# stm32_board.net
KiCad netlist of a schematic drawn in Altium Designer
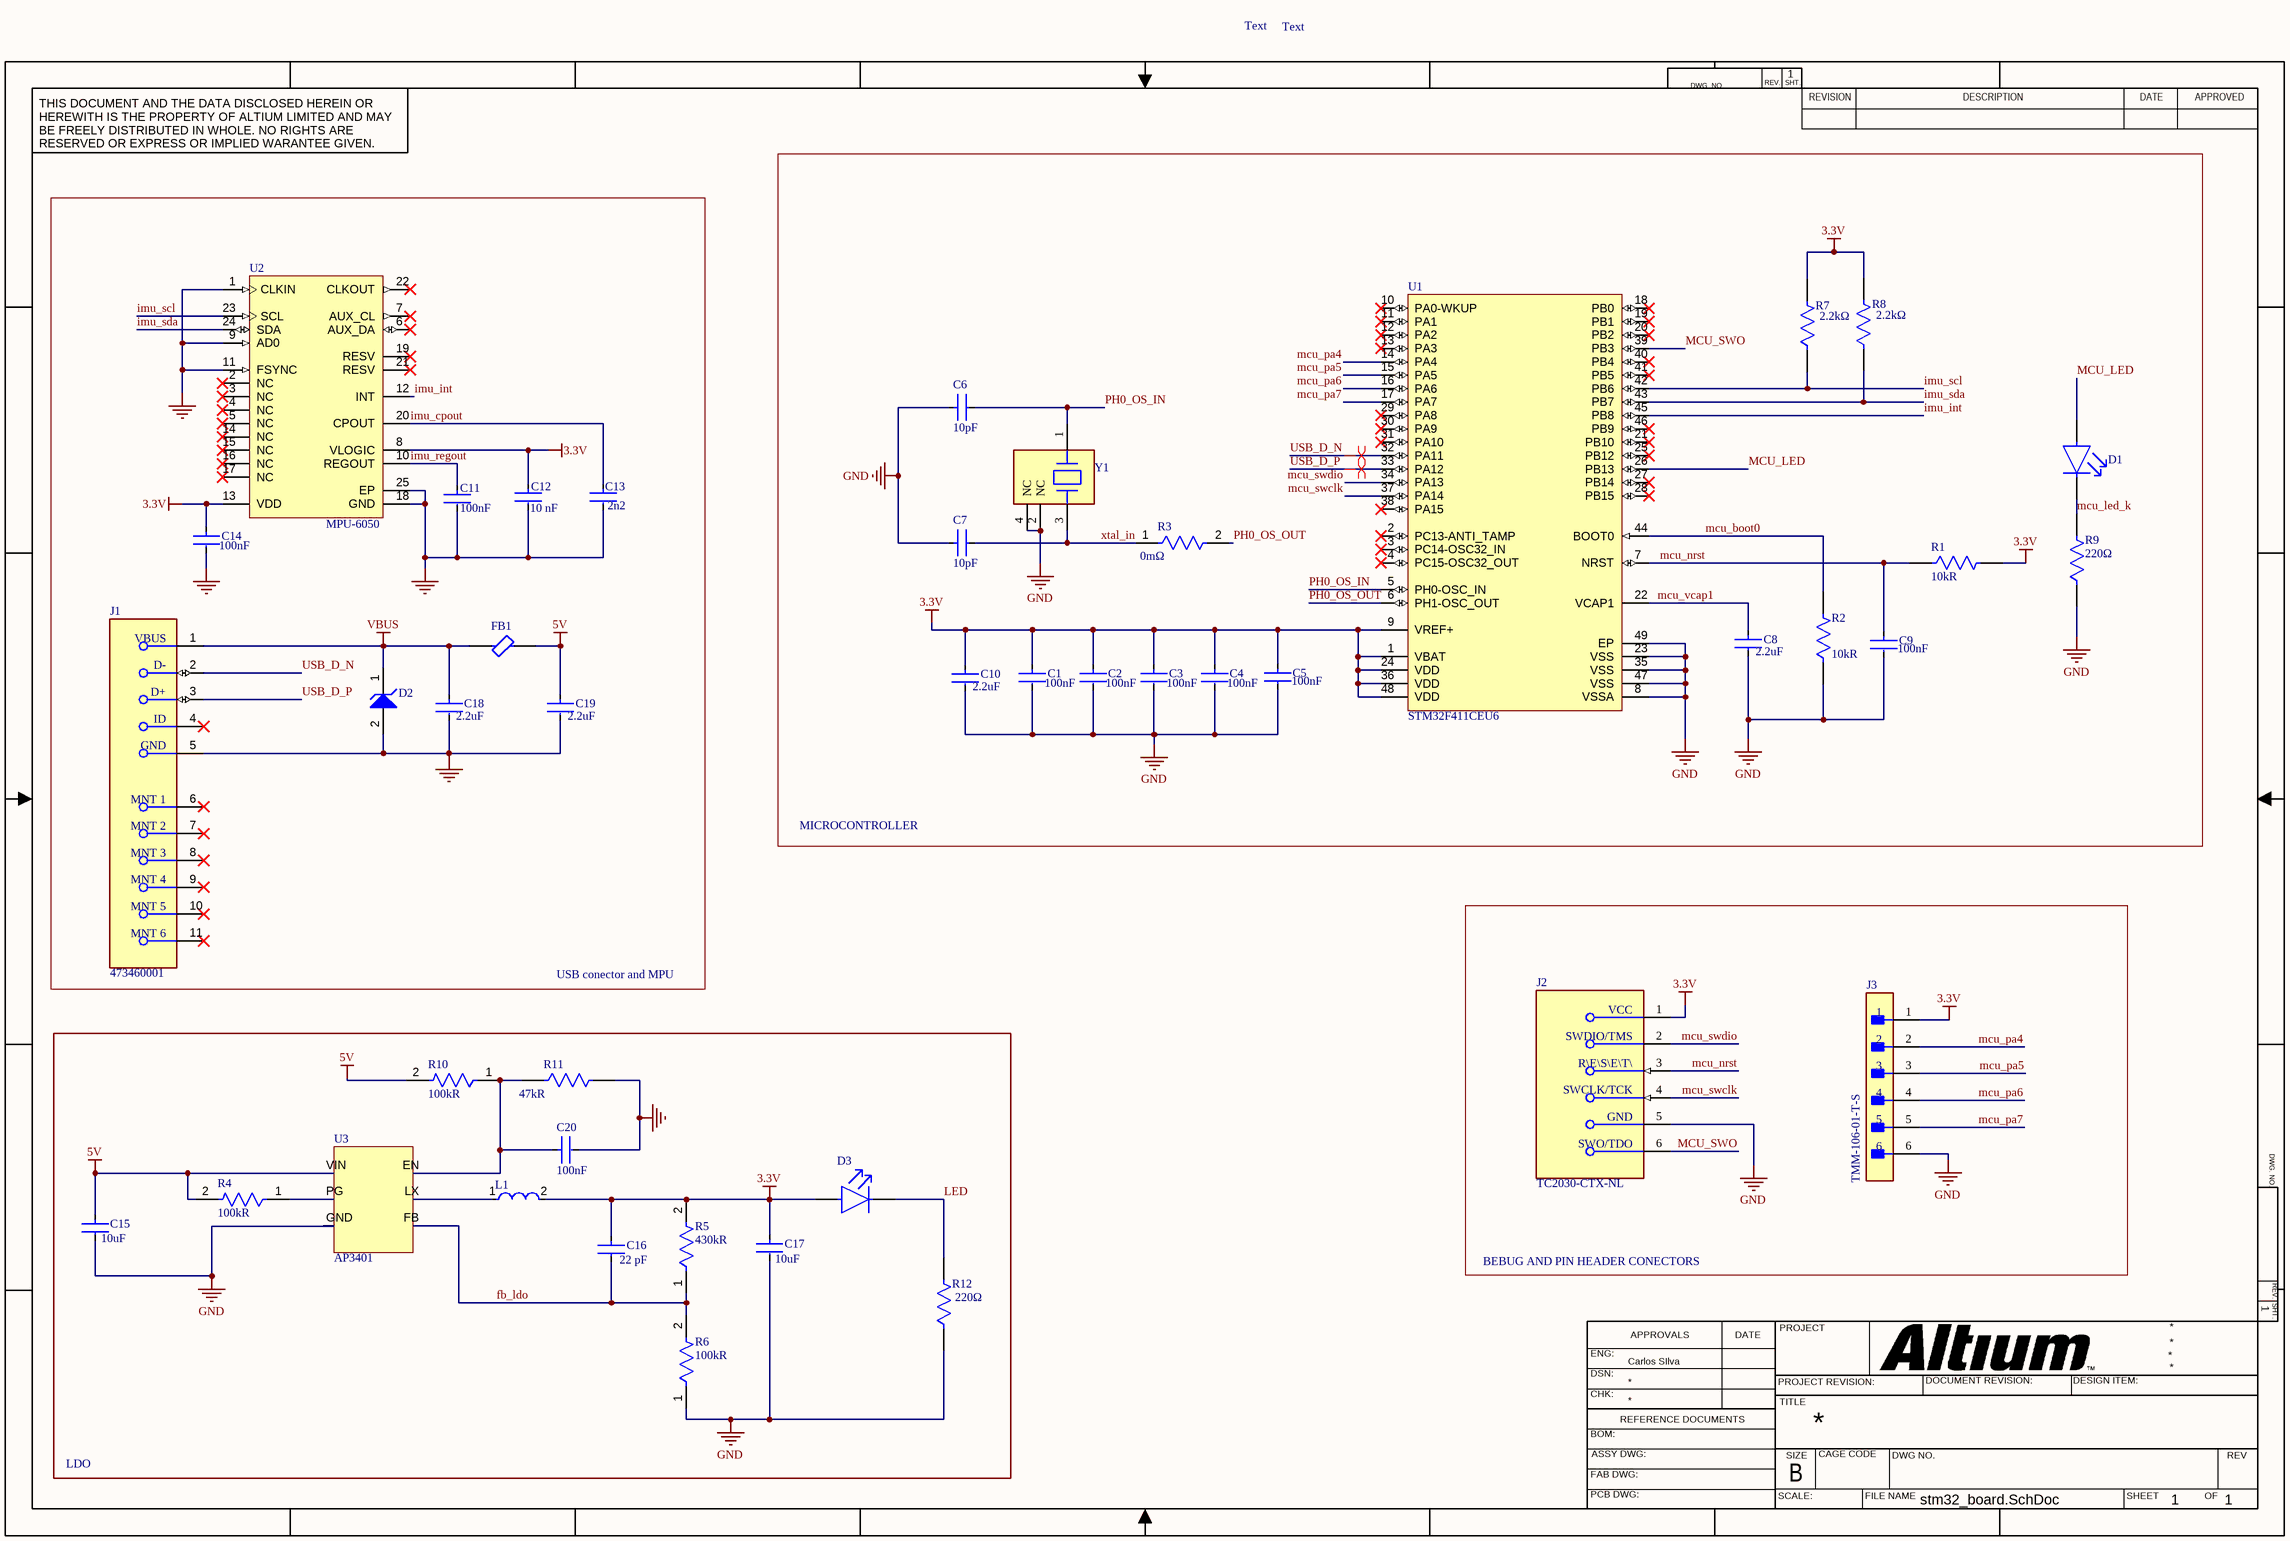
[diagram p0: stm32_board.SchDoc]

(export (version "E")
  (design (tool "Eeschema 10.0.6"))
  (components
    (comp (ref "C1")
      (value "CL05B104KP5NNNC")
      (footprint "FP-CL17-IPC_C")
      (description "Cap Ceramic 100nF 10V X7R ±10% SMD 0402 +125°C Paper T/R")
      (fields (field (name "CAPACITANCE") "100nF") (field (name "TOLERANCE") "10%"))
      (libsource (lib "Altium Content Vault") (part "b4654b650e69147ec39a6b967a45e02"))
    )
    (comp (ref "C2")
      (value "CL05B104KP5NNNC")
      (footprint "FP-CL17-IPC_C")
      (description "Cap Ceramic 100nF 10V X7R ±10% SMD 0402 +125°C Paper T/R")
      (fields (field (name "CAPACITANCE") "100nF") (field (name "TOLERANCE") "10%"))
      (libsource (lib "Altium Content Vault") (part "b4654b650e69147ec39a6b967a45e02"))
    )
    (comp (ref "C3")
      (value "CL05B104KP5NNNC")
      (footprint "FP-CL17-IPC_C")
      (description "Cap Ceramic 100nF 10V X7R ±10% SMD 0402 +125°C Paper T/R")
      (fields (field (name "CAPACITANCE") "100nF") (field (name "TOLERANCE") "10%"))
      (libsource (lib "Altium Content Vault") (part "b4654b650e69147ec39a6b967a45e02"))
    )
    (comp (ref "C4")
      (value "CL05B104KP5NNNC")
      (footprint "FP-CL17-IPC_C")
      (description "Cap Ceramic 100nF 10V X7R ±10% SMD 0402 +125°C Paper T/R")
      (fields (field (name "CAPACITANCE") "100nF") (field (name "TOLERANCE") "10%"))
      (libsource (lib "Altium Content Vault") (part "b4654b650e69147ec39a6b967a45e02"))
    )
    (comp (ref "C5")
      (value "CL05B104KP5NNNC")
      (footprint "FP-CL17-IPC_C")
      (description "Cap Ceramic 100nF 10V X7R ±10% SMD 0402 +125°C Paper T/R")
      (fields (field (name "CAPACITANCE") "100nF") (field (name "TOLERANCE") "10%"))
      (libsource (lib "Altium Content Vault") (part "b4654b650e69147ec39a6b967a45e02"))
    )
    (comp (ref "C6")
      (value "GRM0225C1C100JA03L")
      (footprint "FP-GRM022-0_02-IPC_C")
      (description "Chip Multilayer Ceramic Capacitors for General Purpose, 01005, 10pF, C0G, 30ppm/°C, 5%, 16V")
      (fields (field (name "CAPACITANCE") "10pF") (field (name "TOLERANCE") "5%"))
      (libsource (lib "Altium Content Vault") (part "02cd4be3c70576c341d710602a673aa"))
    )
    (comp (ref "C7")
      (value "GRM0225C1C100JA03L")
      (footprint "FP-GRM022-0_02-IPC_C")
      (description "Chip Multilayer Ceramic Capacitors for General Purpose, 01005, 10pF, C0G, 30ppm/°C, 5%, 16V")
      (fields (field (name "CAPACITANCE") "10pF") (field (name "TOLERANCE") "5%"))
      (libsource (lib "Altium Content Vault") (part "02cd4be3c70576c341d710602a673aa"))
    )
    (comp (ref "C8")
      (value "GRM155D71A225ME15D")
      (footprint "FP-GRM155-0_2-0_05-IPC_A")
      (description "Chip Multilayer Ceramic Capacitors for General Purpose, 0402, 2.2uF, X7T, +22%/-33%, 20%, 10V")
      (fields (field (name "TOLERANCE") "20%") (field (name "CAPACITANCE") "2.2uF"))
      (libsource (lib "Altium Content Vault") (part "b4654b650e69147ec39a6b967a45e02"))
    )
    (comp (ref "C9")
      (value "CL05B104KP5NNNC")
      (footprint "FP-CL17-IPC_C")
      (description "Cap Ceramic 100nF 10V X7R ±10% SMD 0402 +125°C Paper T/R")
      (fields (field (name "CAPACITANCE") "100nF") (field (name "TOLERANCE") "10%"))
      (libsource (lib "Altium Content Vault") (part "b4654b650e69147ec39a6b967a45e02"))
    )
    (comp (ref "C10")
      (value "GRM155D71A225ME15D")
      (footprint "FP-GRM155-0_2-0_05-IPC_A")
      (description "Chip Multilayer Ceramic Capacitors for General Purpose, 0402, 2.2uF, X7T, +22%/-33%, 20%, 10V")
      (fields (field (name "TOLERANCE") "20%") (field (name "CAPACITANCE") "2.2uF"))
      (libsource (lib "Altium Content Vault") (part "b4654b650e69147ec39a6b967a45e02"))
    )
    (comp (ref "C11")
      (value "CL05B104KP5NNNC")
      (footprint "FP-CL17-IPC_C")
      (description "Cap Ceramic 100nF 10V X7R ±10% SMD 0402 +125°C Paper T/R")
      (fields (field (name "CAPACITANCE") "100nF") (field (name "TOLERANCE") "10%"))
      (libsource (lib "Altium Content Vault") (part "b4654b650e69147ec39a6b967a45e02"))
    )
    (comp (ref "C12")
      (value "C0603C103K5RACTU")
      (footprint "FP-C0603C-CF-MFG")
      (description "CAP CER 10000PF 50V X7R 0603")
      (fields
        (field (name "MANUFACTURER") "KEMET")
        (field (name "CAPACITANCE") "10 nF")
        (field (name "OCTOPART") "https://octopart.com/c0603c103k5ractu-kemet-133094")
      )
      (libsource (lib "Altium Content Vault") (part "b4654b650e69147ec39a6b967a45e02"))
    )
    (comp (ref "C13")
      (value "2n2")
      (footprint "FP-C0402-BB-MFG")
      (description "CAP CER 2200PF 16V NP0 0402")
      (fields
        (field (name "OCTOPART") "https://octopart.com/c0402c222f4gactu-kemet-12823119")
        (field (name "MANUFACTURER") "Kemet")
      )
      (libsource (lib "Altium Content Vault") (part "b4654b650e69147ec39a6b967a45e02"))
    )
    (comp (ref "C14")
      (value "CL05B104KP5NNNC")
      (footprint "FP-CL17-IPC_C")
      (description "Cap Ceramic 100nF 10V X7R ±10% SMD 0402 +125°C Paper T/R")
      (fields (field (name "CAPACITANCE") "100nF") (field (name "TOLERANCE") "10%"))
      (libsource (lib "Altium Content Vault") (part "b4654b650e69147ec39a6b967a45e02"))
    )
    (comp (ref "C15")
      (value "LMK107BBJ106MALT")
      (footprint "FP-0603-L_1_6_0_2-W_0_8_0-IPC_A")
      (description "Multilayer Ceramic Capacitor 10uF 10V X5R 20% SMD 0603 T/R")
      (fields
        (field (name "VOLTAGE") "10V")
        (field (name "TOLERANCE") "20%")
        (field (name "CAPACITANCE") "10uF")
      )
      (libsource (lib "Altium Content Vault") (part "b4654b650e69147ec39a6b967a45e02"))
    )
    (comp (ref "C16")
      (value "C0603C220J5GACTU")
      (footprint "FP-C0603C-CF-MFG")
      (description "Cap Ceramic 22pF 50V C0G 5% SMD 0603 125°C Paper T/R")
      (fields
        (field (name "CAPACITANCE") "22 pF")
        (field (name "TOLERANCE") "0.05")
        (field (name "MANUFACTURER") "KEMET")
      )
      (libsource (lib "Altium Content Vault") (part "b4654b650e69147ec39a6b967a45e02"))
    )
    (comp (ref "C17")
      (value "LMK107BBJ106MALT")
      (footprint "FP-0603-L_1_6_0_2-W_0_8_0-IPC_A")
      (description "Multilayer Ceramic Capacitor 10uF 10V X5R 20% SMD 0603 T/R")
      (fields
        (field (name "VOLTAGE") "10V")
        (field (name "TOLERANCE") "20%")
        (field (name "CAPACITANCE") "10uF")
      )
      (libsource (lib "Altium Content Vault") (part "b4654b650e69147ec39a6b967a45e02"))
    )
    (comp (ref "C18")
      (value "GRM155D71A225ME15D")
      (footprint "FP-GRM155-0_2-0_05-IPC_A")
      (description "Chip Multilayer Ceramic Capacitors for General Purpose, 0402, 2.2uF, X7T, +22%/-33%, 20%, 10V")
      (fields (field (name "TOLERANCE") "20%") (field (name "CAPACITANCE") "2.2uF"))
      (libsource (lib "Altium Content Vault") (part "b4654b650e69147ec39a6b967a45e02"))
    )
    (comp (ref "C19")
      (value "GRM155D71A225ME15D")
      (footprint "FP-GRM155-0_2-0_05-IPC_A")
      (description "Chip Multilayer Ceramic Capacitors for General Purpose, 0402, 2.2uF, X7T, +22%/-33%, 20%, 10V")
      (fields (field (name "TOLERANCE") "20%") (field (name "CAPACITANCE") "2.2uF"))
      (libsource (lib "Altium Content Vault") (part "b4654b650e69147ec39a6b967a45e02"))
    )
    (comp (ref "C20")
      (value "CL05B104KP5NNNC")
      (footprint "FP-CL17-IPC_C")
      (description "Cap Ceramic 100nF 10V X7R ±10% SMD 0402 +125°C Paper T/R")
      (fields (field (name "CAPACITANCE") "100nF") (field (name "TOLERANCE") "10%"))
      (libsource (lib "Altium Content Vault") (part "b4654b650e69147ec39a6b967a45e02"))
    )
    (comp (ref "D1")
      (value "LTST-C190GKT")
      (footprint "FP-LTST-C190GKT-MFG")
      (description "LED GREEN CLEAR CHIP SMD")
      (fields (field (name "VOLTAGE") "2V"))
      (libsource (lib "Altium Content Vault") (part "8706943c75ba83719d021d2fdc84c58"))
    )
    (comp (ref "D2")
      (value "ESD9X5.0ST5G")
      (footprint "ONSC-SOD-923-2-514AA-01_V")
      (fields (field (name "MANUFACTURER") "On Semiconductor"))
      (libsource (lib "Altium Content Vault") (part "ONSC-K1A2-2"))
    )
    (comp (ref "D3")
      (value "LTST-C190GKT")
      (footprint "FP-LTST-C190GKT-MFG")
      (description "LED GREEN CLEAR CHIP SMD")
      (fields (field (name "VOLTAGE") "2V"))
      (libsource (lib "Altium Content Vault") (part "8706943c75ba83719d021d2fdc84c58"))
    )
    (comp (ref "FB1")
      (value "BLM18KG121TN1D")
      (footprint "FP-BLM18-0_15-t0_6-d1_2-IPC_A")
      (description "FERRITE BEAD 120 OHM 0603 1LN")
      (fields (field (name "TOLERANCE") "25%"))
      (libsource (lib "Altium Content Vault") (part "5f30dd21d616792df468990f7003faa"))
    )
    (comp (ref "J1")
      (value "473460001")
      (footprint "FP-473460001-MFG")
      (description "CONN RCPT USB2.0 MICRO B SMD R/A")
      (fields
        (field (name "OCTOPART") "https://octopart.com/47346-0001-molex-7164928")
        (field (name "MANUFACTURER") "Molex")
      )
      (libsource (lib "Altium Content Vault") (part "53ae1f1d9b557310b43ca686e5bb76a"))
    )
    (comp (ref "J2")
      (value "TC2030-CTX-NL")
      (footprint "FP-TC2030-CTX-NL-MFG")
      (description "6-Pin “No legs” TC2030 Plug-of-Nails™ Cable for use with ARM Cortex processors")
      (libsource (lib "Altium Content Vault") (part "e3fe093a55dc37473f431e03719485e"))
    )
    (comp (ref "J3")
      (value "TMM-106-01-T-S")
      (footprint "FP-TMM-106-01-T-S-MFG")
      (description "CONN HEADER VERT 6POS 2MM")
      (libsource (lib "Altium Content Vault") (part "f2cb566baf1c37ab5a3b8e90bbeafd6"))
    )
    (comp (ref "L1")
      (value "LQM2MPN2R2NG0L")
      (footprint "FP-LQM2MPN_G0-MFG")
      (description "Multilayer Type Inductor for Power Lines, 0806 (2016), 2.2μH, 30%, 0.138Ω, 1.2A")
      (fields (field (name "TOLERANCE") "30%"))
      (libsource (lib "Altium Content Vault") (part "725321dda6339637d4d059423bc1c3c"))
    )
    (comp (ref "R1")
      (value "RMCF0603FT10K0")
      (footprint "FP-RMCF0603-MFG")
      (description "10kΩ ±1% 0.1W 0603 Thick Film Chip Resistor AEC-Q200 compliant")
      (fields (field (name "RESISTANCE") "10kR") (field (name "TOLERANCE") "1%"))
      (libsource (lib "") (part "1029c3af85768c4190bb7ad29bc67b5_1"))
    )
    (comp (ref "R2")
      (value "RMCF0603FT10K0")
      (footprint "FP-RMCF0603-MFG")
      (description "10kΩ ±1% 0.1W 0603 Thick Film Chip Resistor AEC-Q200 compliant")
      (fields (field (name "RESISTANCE") "10kR") (field (name "TOLERANCE") "1%"))
      (libsource (lib "") (part "1029c3af85768c4190bb7ad29bc67b5_1"))
    )
    (comp (ref "R3")
      (value "RMCF0603ZT0R00")
      (footprint "FP-RMCF0603-MFG")
      (description "RES 0 OHM JUMPER 1/10W 0603")
      (fields
        (field (name "OCTOPART") "https://octopart.com/rmcf0603zt0r00-stackpole+electronics-19213618")
        (field (name "MANUFACTURER") "Stackpole")
        (field (name "RESISTANCE") "0mΩ")
      )
      (libsource (lib "Altium Content Vault") (part "1029c3af85768c4190bb7ad29bc67b5"))
    )
    (comp (ref "R4")
      (value "RMCF0603FT100K")
      (footprint "FP-RMCF0603-IPC_C")
      (description "100kΩ ±1% 0.1W 0603 Thick Film Chip Resistor AEC-Q200 compliant")
      (fields (field (name "TOLERANCE") "1%") (field (name "RESISTANCE") "100kR"))
      (libsource (lib "Altium Content Vault") (part "1029c3af85768c4190bb7ad29bc67b5"))
    )
    (comp (ref "R5")
      (value "KTR25JZPF4303")
      (footprint "FP-KTR25-MFG")
      (description "Res Thick Film 1210 430kΩ 1% 0.1W ±100ppm/°C Automotive Embossed T/R")
      (fields (field (name "TOLERANCE") "1%") (field (name "RESISTANCE") "430kR"))
      (libsource (lib "Altium Content Vault") (part "1029c3af85768c4190bb7ad29bc67b5"))
    )
    (comp (ref "R6")
      (value "RMCF0603FT100K")
      (footprint "FP-RMCF0603-IPC_C")
      (description "100kΩ ±1% 0.1W 0603 Thick Film Chip Resistor AEC-Q200 compliant")
      (fields (field (name "TOLERANCE") "1%") (field (name "RESISTANCE") "100kR"))
      (libsource (lib "Altium Content Vault") (part "1029c3af85768c4190bb7ad29bc67b5"))
    )
    (comp (ref "R7")
      (value "2.2kΩ")
      (footprint "FP-ERA2A-MFG")
      (description "RES SMD 2.2K OHM 0.1% 1/16W 0402")
      (fields (field (name "TOLERANCE") "0.1%") (field (name "MANUFACTURER PART NUMBER") "ERA-2AEB222X"))
      (libsource (lib "") (part "1029c3af85768c4190bb7ad29bc67b5_1"))
    )
    (comp (ref "R8")
      (value "2.2kΩ")
      (footprint "FP-ERA2A-MFG")
      (description "RES SMD 2.2K OHM 0.1% 1/16W 0402")
      (fields (field (name "TOLERANCE") "0.1%") (field (name "MANUFACTURER PART NUMBER") "ERA-2AEB222X"))
      (libsource (lib "") (part "1029c3af85768c4190bb7ad29bc67b5_1"))
    )
    (comp (ref "R9")
      (value "CRGCQ0402J220R")
      (footprint "FP-CRGCQ0402-IPC_C")
      (description "CRGCQ 0402 220R 5%")
      (fields
        (field (name "TOLERANCE") "0.05")
        (field (name "OCTOPART") "https://octopart.com/crgcq0402j220r-te+connectivity-91018007")
        (field (name "RESISTANCE") "220Ω")
      )
      (libsource (lib "") (part "1029c3af85768c4190bb7ad29bc67b5_1"))
    )
    (comp (ref "R10")
      (value "RMCF0603FT100K")
      (footprint "FP-RMCF0603-IPC_C")
      (description "100kΩ ±1% 0.1W 0603 Thick Film Chip Resistor AEC-Q200 compliant")
      (fields (field (name "TOLERANCE") "1%") (field (name "RESISTANCE") "100kR"))
      (libsource (lib "Altium Content Vault") (part "1029c3af85768c4190bb7ad29bc67b5"))
    )
    (comp (ref "R11")
      (value "RC0603FR-0747KL")
      (footprint "FP-RC0603FR-0747KL-MFG")
      (description "RES SMD 47K OHM 1% 1/10W 0603")
      (fields (field (name "TOLERANCE") "1%") (field (name "RESISTANCE") "47kR"))
      (libsource (lib "") (part "1029c3af85768c4190bb7ad29bc67b5_1"))
    )
    (comp (ref "R12")
      (value "CRGCQ0402J220R")
      (footprint "FP-CRGCQ0402-IPC_C")
      (description "CRGCQ 0402 220R 5%")
      (fields
        (field (name "TOLERANCE") "0.05")
        (field (name "OCTOPART") "https://octopart.com/crgcq0402j220r-te+connectivity-91018007")
        (field (name "RESISTANCE") "220Ω")
      )
      (libsource (lib "") (part "1029c3af85768c4190bb7ad29bc67b5_1"))
    )
    (comp (ref "U1")
      (value "STM32F411CEU6")
      (footprint "STM-UFQFPN48_L")
      (libsource (lib "Altium Content Vault") (part "MC-ARM-STM32F411-UFQFPN48"))
    )
    (comp (ref "U2")
      (value "MPU-6050")
      (footprint "IS-QFN-24_V")
      (fields (field (name "MANUFACTURER") "InvenSense"))
      (libsource (lib "Altium Content Vault") (part "IS-MPU-6050-QFN-24"))
    )
    (comp (ref "U3")
      (value "AP3401")
      (footprint "AP3401")
      (description "1.5MHZ, 1A STEP-DOWN DC - DC BUCK CONVERTER")
      (libsource (lib "Mi_Libreria") (part "AP3401"))
    )
    (comp (ref "Y1")
      (value "XRCGB24M000F3M00R0")
      (footprint "FP-XRCGB_F_N-MFG")
      (description "CRYSTAL 24.0000MHZ 6PF SMD")
      (fields (field (name "TOLERANCE") "30ppm"))
      (libsource (lib "Altium Content Vault") (part "13d16a3a70fb0809ccfd81e284aeb9d"))
    )
  )
  (nets
    (net (code "1") (name "/LED") (class "Default")
      (node (ref "D3") (pin "1") (pinfunction "C_1") (pintype "passive"))
      (node (ref "R12") (pin "2") (pinfunction "2_2") (pintype "passive"))
    )
    (net (code "2") (name "/MCU_LED") (class "Default")
      (node (ref "D1") (pin "2") (pinfunction "A_2") (pintype "passive"))
      (node (ref "U1") (pin "26") (pinfunction "PB13_26") (pintype "bidirectional"))
    )
    (net (code "3") (name "/MCU_SWO") (class "Default")
      (node (ref "J2") (pin "6") (pinfunction "SWO/TDO_6") (pintype "passive"))
      (node (ref "U1") (pin "39") (pinfunction "PB3_39") (pintype "bidirectional"))
    )
    (net (code "4") (name "/PH0_OS_IN") (class "Default")
      (node (ref "C6") (pin "2") (pinfunction "2_2") (pintype "passive"))
      (node (ref "U1") (pin "5") (pinfunction "PH0-OSC_IN_5") (pintype "bidirectional"))
      (node (ref "Y1") (pin "1") (pinfunction "1_Input/Output_1") (pintype "passive"))
    )
    (net (code "5") (name "/PH0_OS_OUT") (class "Default")
      (node (ref "R3") (pin "2") (pinfunction "2_2") (pintype "passive"))
      (node (ref "U1") (pin "6") (pinfunction "PH1-OSC_OUT_6") (pintype "bidirectional"))
    )
    (net (code "6") (name "/USB_D_N") (class "Default")
      (node (ref "J1") (pin "2") (pinfunction "D-_2") (pintype "bidirectional"))
      (node (ref "U1") (pin "32") (pinfunction "PA11_32") (pintype "bidirectional"))
    )
    (net (code "7") (name "/USB_D_P") (class "Default")
      (node (ref "J1") (pin "3") (pinfunction "D+_3") (pintype "bidirectional"))
      (node (ref "U1") (pin "33") (pinfunction "PA12_33") (pintype "bidirectional"))
    )
    (net (code "8") (name "/fb_ldo") (class "Default")
      (node (ref "C16") (pin "2") (pinfunction "2_2") (pintype "passive"))
      (node (ref "R5") (pin "1") (pinfunction "1_1") (pintype "passive"))
      (node (ref "R6") (pin "2") (pinfunction "2_2") (pintype "passive"))
      (node (ref "U3") (pin "FB") (pinfunction "FB_FB") (pintype "passive"))
    )
    (net (code "9") (name "/imu_cpout") (class "Default")
      (node (ref "C13") (pin "1") (pinfunction "1_1") (pintype "passive"))
      (node (ref "U2") (pin "20") (pinfunction "CPOUT_20") (pintype "passive"))
    )
    (net (code "10") (name "/imu_int") (class "Default")
      (node (ref "U1") (pin "45") (pinfunction "PB8_45") (pintype "bidirectional"))
      (node (ref "U2") (pin "12") (pinfunction "INT_12") (pintype "open_collector"))
    )
    (net (code "11") (name "/imu_regout") (class "Default")
      (node (ref "C11") (pin "1") (pinfunction "1_1") (pintype "passive"))
      (node (ref "U2") (pin "10") (pinfunction "REGOUT_10") (pintype "passive"))
    )
    (net (code "12") (name "/imu_scl") (class "Default")
      (node (ref "R7") (pin "1") (pinfunction "1_1") (pintype "passive"))
      (node (ref "U1") (pin "42") (pinfunction "PB6_42") (pintype "bidirectional"))
      (node (ref "U2") (pin "23") (pinfunction "SCL_23") (pintype "input"))
    )
    (net (code "13") (name "/imu_sda") (class "Default")
      (node (ref "R8") (pin "1") (pinfunction "1_1") (pintype "passive"))
      (node (ref "U1") (pin "43") (pinfunction "PB7_43") (pintype "bidirectional"))
      (node (ref "U2") (pin "24") (pinfunction "SDA_24") (pintype "bidirectional"))
    )
    (net (code "14") (name "/mcu_boot0") (class "Default")
      (node (ref "R2") (pin "2") (pinfunction "2_2") (pintype "passive"))
      (node (ref "U1") (pin "44") (pinfunction "BOOT0_44") (pintype "input"))
    )
    (net (code "15") (name "/mcu_led_k") (class "Default")
      (node (ref "D1") (pin "1") (pinfunction "C_1") (pintype "passive"))
      (node (ref "R9") (pin "2") (pinfunction "2_2") (pintype "passive"))
    )
    (net (code "16") (name "/mcu_nrst") (class "Default")
      (node (ref "C9") (pin "1") (pinfunction "1_1") (pintype "passive"))
      (node (ref "J2") (pin "3") (pinfunction "~{RESET}_3") (pintype "input"))
      (node (ref "R1") (pin "1") (pinfunction "1_1") (pintype "passive"))
      (node (ref "U1") (pin "7") (pinfunction "NRST_7") (pintype "bidirectional"))
    )
    (net (code "17") (name "/mcu_pa4") (class "Default")
      (node (ref "J3") (pin "2") (pinfunction "2_2") (pintype "passive"))
      (node (ref "U1") (pin "14") (pinfunction "PA4_14") (pintype "bidirectional"))
    )
    (net (code "18") (name "/mcu_pa5") (class "Default")
      (node (ref "J3") (pin "3") (pinfunction "3_3") (pintype "passive"))
      (node (ref "U1") (pin "15") (pinfunction "PA5_15") (pintype "bidirectional"))
    )
    (net (code "19") (name "/mcu_pa6") (class "Default")
      (node (ref "J3") (pin "4") (pinfunction "4_4") (pintype "passive"))
      (node (ref "U1") (pin "16") (pinfunction "PA6_16") (pintype "bidirectional"))
    )
    (net (code "20") (name "/mcu_pa7") (class "Default")
      (node (ref "J3") (pin "5") (pinfunction "5_5") (pintype "passive"))
      (node (ref "U1") (pin "17") (pinfunction "PA7_17") (pintype "bidirectional"))
    )
    (net (code "21") (name "/mcu_swclk") (class "Default")
      (node (ref "J2") (pin "4") (pinfunction "SWCLK/TCK_4") (pintype "input"))
      (node (ref "U1") (pin "37") (pinfunction "PA14_37") (pintype "bidirectional"))
    )
    (net (code "22") (name "/mcu_swdio") (class "Default")
      (node (ref "J2") (pin "2") (pinfunction "SWDIO/TMS_2") (pintype "passive"))
      (node (ref "U1") (pin "34") (pinfunction "PA13_34") (pintype "bidirectional"))
    )
    (net (code "23") (name "/mcu_vcap1") (class "Default")
      (node (ref "C8") (pin "1") (pinfunction "1_1") (pintype "passive"))
      (node (ref "U1") (pin "22") (pinfunction "VCAP1_22") (pintype "passive"))
    )
    (net (code "24") (name "/xtal_in") (class "Default")
      (node (ref "C7") (pin "2") (pinfunction "2_2") (pintype "passive"))
      (node (ref "R3") (pin "1") (pinfunction "1_1") (pintype "passive"))
      (node (ref "Y1") (pin "3") (pinfunction "2_Input/Output_3") (pintype "passive"))
    )
    (net (code "25") (name "3.3V") (class "Default")
      (node (ref "C1") (pin "1") (pinfunction "1_1") (pintype "passive"))
      (node (ref "C10") (pin "1") (pinfunction "1_1") (pintype "passive"))
      (node (ref "C12") (pin "1") (pinfunction "1_1") (pintype "passive"))
      (node (ref "C14") (pin "1") (pinfunction "1_1") (pintype "passive"))
      (node (ref "C16") (pin "1") (pinfunction "1_1") (pintype "passive"))
      (node (ref "C17") (pin "1") (pinfunction "1_1") (pintype "passive"))
      (node (ref "C2") (pin "1") (pinfunction "1_1") (pintype "passive"))
      (node (ref "C3") (pin "1") (pinfunction "1_1") (pintype "passive"))
      (node (ref "C4") (pin "1") (pinfunction "1_1") (pintype "passive"))
      (node (ref "C5") (pin "1") (pinfunction "1_1") (pintype "passive"))
      (node (ref "D3") (pin "2") (pinfunction "A_2") (pintype "passive"))
      (node (ref "J2") (pin "1") (pinfunction "VCC_1") (pintype "power_in"))
      (node (ref "J3") (pin "1") (pinfunction "1_1") (pintype "passive"))
      (node (ref "L1") (pin "2") (pinfunction "2_2") (pintype "passive"))
      (node (ref "R1") (pin "2") (pinfunction "2_2") (pintype "passive"))
      (node (ref "R5") (pin "2") (pinfunction "2_2") (pintype "passive"))
      (node (ref "R7") (pin "2") (pinfunction "2_2") (pintype "passive"))
      (node (ref "R8") (pin "2") (pinfunction "2_2") (pintype "passive"))
      (node (ref "U1") (pin "1") (pinfunction "VBAT_1") (pintype "power_in"))
      (node (ref "U1") (pin "24") (pinfunction "VDD_24") (pintype "power_in"))
      (node (ref "U1") (pin "36") (pinfunction "VDD_36") (pintype "power_in"))
      (node (ref "U1") (pin "48") (pinfunction "VDD_48") (pintype "power_in"))
      (node (ref "U1") (pin "9") (pinfunction "VREF+_9") (pintype "power_in"))
      (node (ref "U2") (pin "13") (pinfunction "VDD_13") (pintype "power_in"))
      (node (ref "U2") (pin "8") (pinfunction "VLOGIC_8") (pintype "power_in"))
    )
    (net (code "26") (name "5V") (class "Default")
      (node (ref "C15") (pin "1") (pinfunction "1_1") (pintype "passive"))
      (node (ref "C19") (pin "1") (pinfunction "1_1") (pintype "passive"))
      (node (ref "FB1") (pin "2") (pinfunction "2_2") (pintype "passive"))
      (node (ref "R10") (pin "2") (pinfunction "2_2") (pintype "passive"))
      (node (ref "R4") (pin "2") (pinfunction "2_2") (pintype "passive"))
      (node (ref "U3") (pin "VIN") (pinfunction "VIN_VIN") (pintype "power_in"))
    )
    (net (code "27") (name "GND") (class "Default")
      (node (ref "C1") (pin "2") (pinfunction "2_2") (pintype "passive"))
      (node (ref "C10") (pin "2") (pinfunction "2_2") (pintype "passive"))
      (node (ref "C11") (pin "2") (pinfunction "2_2") (pintype "passive"))
      (node (ref "C12") (pin "2") (pinfunction "2_2") (pintype "passive"))
      (node (ref "C13") (pin "2") (pinfunction "2_2") (pintype "passive"))
      (node (ref "C14") (pin "2") (pinfunction "2_2") (pintype "passive"))
      (node (ref "C15") (pin "2") (pinfunction "2_2") (pintype "passive"))
      (node (ref "C17") (pin "2") (pinfunction "2_2") (pintype "passive"))
      (node (ref "C18") (pin "2") (pinfunction "2_2") (pintype "passive"))
      (node (ref "C19") (pin "2") (pinfunction "2_2") (pintype "passive"))
      (node (ref "C2") (pin "2") (pinfunction "2_2") (pintype "passive"))
      (node (ref "C20") (pin "2") (pinfunction "2_2") (pintype "passive"))
      (node (ref "C3") (pin "2") (pinfunction "2_2") (pintype "passive"))
      (node (ref "C4") (pin "2") (pinfunction "2_2") (pintype "passive"))
      (node (ref "C5") (pin "2") (pinfunction "2_2") (pintype "passive"))
      (node (ref "C6") (pin "1") (pinfunction "1_1") (pintype "passive"))
      (node (ref "C7") (pin "1") (pinfunction "1_1") (pintype "passive"))
      (node (ref "C8") (pin "2") (pinfunction "2_2") (pintype "passive"))
      (node (ref "C9") (pin "2") (pinfunction "2_2") (pintype "passive"))
      (node (ref "D2") (pin "2") (pinfunction "A_2") (pintype "passive"))
      (node (ref "J1") (pin "5") (pinfunction "GND_5") (pintype "power_in"))
      (node (ref "J2") (pin "5") (pinfunction "GND_5") (pintype "power_in"))
      (node (ref "J3") (pin "6") (pinfunction "6_6") (pintype "passive"))
      (node (ref "R11") (pin "2") (pinfunction "2_2") (pintype "passive"))
      (node (ref "R12") (pin "1") (pinfunction "1_1") (pintype "passive"))
      (node (ref "R2") (pin "1") (pinfunction "1_1") (pintype "passive"))
      (node (ref "R6") (pin "1") (pinfunction "1_1") (pintype "passive"))
      (node (ref "R9") (pin "1") (pinfunction "1_1") (pintype "passive"))
      (node (ref "U1") (pin "23") (pinfunction "VSS_23") (pintype "power_in"))
      (node (ref "U1") (pin "35") (pinfunction "VSS_35") (pintype "power_in"))
      (node (ref "U1") (pin "47") (pinfunction "VSS_47") (pintype "power_in"))
      (node (ref "U1") (pin "49") (pinfunction "EP_49") (pintype "power_in"))
      (node (ref "U1") (pin "8") (pinfunction "VSSA_8") (pintype "power_in"))
      (node (ref "U2") (pin "1") (pinfunction "CLKIN_1") (pintype "input"))
      (node (ref "U2") (pin "11") (pinfunction "FSYNC_11") (pintype "input"))
      (node (ref "U2") (pin "18") (pinfunction "GND_18") (pintype "power_in"))
      (node (ref "U2") (pin "25") (pinfunction "EP_25") (pintype "power_in"))
      (node (ref "U2") (pin "9") (pinfunction "AD0_9") (pintype "input"))
      (node (ref "U3") (pin "GND") (pinfunction "GND_GND") (pintype "power_in"))
      (node (ref "Y1") (pin "2") (pinfunction "NC_2") (pintype "passive"))
      (node (ref "Y1") (pin "4") (pinfunction "NC_4") (pintype "passive"))
    )
    (net (code "28") (name "Net-(C20-Pad1)") (class "Default")
      (node (ref "C20") (pin "1") (pinfunction "1_1") (pintype "passive"))
      (node (ref "R10") (pin "1") (pinfunction "1_1") (pintype "passive"))
      (node (ref "R11") (pin "1") (pinfunction "1_1") (pintype "passive"))
      (node (ref "U3") (pin "EN") (pinfunction "EN_EN") (pintype "input"))
    )
    (net (code "29") (name "Net-(L1-Pad1)") (class "Default")
      (node (ref "L1") (pin "1") (pinfunction "1_1") (pintype "passive"))
      (node (ref "U3") (pin "LX") (pinfunction "LX_LX") (pintype "output"))
    )
    (net (code "30") (name "Net-(R4-Pad1)") (class "Default")
      (node (ref "R4") (pin "1") (pinfunction "1_1") (pintype "passive"))
      (node (ref "U3") (pin "PG") (pinfunction "PG_PG") (pintype "passive"))
    )
    (net (code "31") (name "VBUS") (class "Default")
      (node (ref "C18") (pin "1") (pinfunction "1_1") (pintype "passive"))
      (node (ref "D2") (pin "1") (pinfunction "K_1") (pintype "passive"))
      (node (ref "FB1") (pin "1") (pinfunction "1_1") (pintype "passive"))
      (node (ref "J1") (pin "1") (pinfunction "VBUS_1") (pintype "power_in"))
    )
    (net (code "32") (name "unconnected-(J1-ID-Pad4)") (class "Default")
      (node (ref "J1") (pin "4") (pinfunction "ID_4") (pintype "passive+no_connect"))
    )
    (net (code "33") (name "unconnected-(J1-MNT_1-Pad6)") (class "Default")
      (node (ref "J1") (pin "6") (pinfunction "MNT_1_6") (pintype "passive+no_connect"))
    )
    (net (code "34") (name "unconnected-(J1-MNT_2-Pad7)") (class "Default")
      (node (ref "J1") (pin "7") (pinfunction "MNT_2_7") (pintype "passive+no_connect"))
    )
    (net (code "35") (name "unconnected-(J1-MNT_3-Pad8)") (class "Default")
      (node (ref "J1") (pin "8") (pinfunction "MNT_3_8") (pintype "passive+no_connect"))
    )
    (net (code "36") (name "unconnected-(J1-MNT_4-Pad9)") (class "Default")
      (node (ref "J1") (pin "9") (pinfunction "MNT_4_9") (pintype "passive+no_connect"))
    )
    (net (code "37") (name "unconnected-(J1-MNT_5-Pad10)") (class "Default")
      (node (ref "J1") (pin "10") (pinfunction "MNT_5_10") (pintype "passive+no_connect"))
    )
    (net (code "38") (name "unconnected-(J1-MNT_6-Pad11)") (class "Default")
      (node (ref "J1") (pin "11") (pinfunction "MNT_6_11") (pintype "passive+no_connect"))
    )
    (net (code "39") (name "unconnected-(U1-PA0-WKUP-Pad10)") (class "Default")
      (node (ref "U1") (pin "10") (pinfunction "PA0-WKUP_10") (pintype "bidirectional+no_connect"))
    )
    (net (code "40") (name "unconnected-(U1-PA1-Pad11)") (class "Default")
      (node (ref "U1") (pin "11") (pinfunction "PA1_11") (pintype "bidirectional+no_connect"))
    )
    (net (code "41") (name "unconnected-(U1-PA2-Pad12)") (class "Default")
      (node (ref "U1") (pin "12") (pinfunction "PA2_12") (pintype "bidirectional+no_connect"))
    )
    (net (code "42") (name "unconnected-(U1-PA3-Pad13)") (class "Default")
      (node (ref "U1") (pin "13") (pinfunction "PA3_13") (pintype "bidirectional+no_connect"))
    )
    (net (code "43") (name "unconnected-(U1-PA8-Pad29)") (class "Default")
      (node (ref "U1") (pin "29") (pinfunction "PA8_29") (pintype "bidirectional+no_connect"))
    )
    (net (code "44") (name "unconnected-(U1-PA9-Pad30)") (class "Default")
      (node (ref "U1") (pin "30") (pinfunction "PA9_30") (pintype "bidirectional+no_connect"))
    )
    (net (code "45") (name "unconnected-(U1-PA10-Pad31)") (class "Default")
      (node (ref "U1") (pin "31") (pinfunction "PA10_31") (pintype "bidirectional+no_connect"))
    )
    (net (code "46") (name "unconnected-(U1-PA15-Pad38)") (class "Default")
      (node (ref "U1") (pin "38") (pinfunction "PA15_38") (pintype "bidirectional+no_connect"))
    )
    (net (code "47") (name "unconnected-(U1-PB0-Pad18)") (class "Default")
      (node (ref "U1") (pin "18") (pinfunction "PB0_18") (pintype "bidirectional+no_connect"))
    )
    (net (code "48") (name "unconnected-(U1-PB1-Pad19)") (class "Default")
      (node (ref "U1") (pin "19") (pinfunction "PB1_19") (pintype "bidirectional+no_connect"))
    )
    (net (code "49") (name "unconnected-(U1-PB2-Pad20)") (class "Default")
      (node (ref "U1") (pin "20") (pinfunction "PB2_20") (pintype "bidirectional+no_connect"))
    )
    (net (code "50") (name "unconnected-(U1-PB4-Pad40)") (class "Default")
      (node (ref "U1") (pin "40") (pinfunction "PB4_40") (pintype "bidirectional+no_connect"))
    )
    (net (code "51") (name "unconnected-(U1-PB5-Pad41)") (class "Default")
      (node (ref "U1") (pin "41") (pinfunction "PB5_41") (pintype "bidirectional+no_connect"))
    )
    (net (code "52") (name "unconnected-(U1-PB9-Pad46)") (class "Default")
      (node (ref "U1") (pin "46") (pinfunction "PB9_46") (pintype "bidirectional+no_connect"))
    )
    (net (code "53") (name "unconnected-(U1-PB10-Pad21)") (class "Default")
      (node (ref "U1") (pin "21") (pinfunction "PB10_21") (pintype "bidirectional+no_connect"))
    )
    (net (code "54") (name "unconnected-(U1-PB12-Pad25)") (class "Default")
      (node (ref "U1") (pin "25") (pinfunction "PB12_25") (pintype "bidirectional+no_connect"))
    )
    (net (code "55") (name "unconnected-(U1-PB14-Pad27)") (class "Default")
      (node (ref "U1") (pin "27") (pinfunction "PB14_27") (pintype "bidirectional+no_connect"))
    )
    (net (code "56") (name "unconnected-(U1-PB15-Pad28)") (class "Default")
      (node (ref "U1") (pin "28") (pinfunction "PB15_28") (pintype "bidirectional+no_connect"))
    )
    (net (code "57") (name "unconnected-(U1-PC13-ANTI_TAMP-Pad2)") (class "Default")
      (node (ref "U1") (pin "2") (pinfunction "PC13-ANTI_TAMP_2") (pintype "bidirectional+no_connect"))
    )
    (net (code "58") (name "unconnected-(U1-PC14-OSC32_IN-Pad3)") (class "Default")
      (node (ref "U1") (pin "3") (pinfunction "PC14-OSC32_IN_3") (pintype "bidirectional+no_connect"))
    )
    (net (code "59") (name "unconnected-(U1-PC15-OSC32_OUT-Pad4)") (class "Default")
      (node (ref "U1") (pin "4") (pinfunction "PC15-OSC32_OUT_4") (pintype "bidirectional+no_connect"))
    )
    (net (code "60") (name "unconnected-(U2-AUX_CL-Pad7)") (class "Default")
      (node (ref "U2") (pin "7") (pinfunction "AUX_CL_7") (pintype "output+no_connect"))
    )
    (net (code "61") (name "unconnected-(U2-AUX_DA-Pad6)") (class "Default")
      (node (ref "U2") (pin "6") (pinfunction "AUX_DA_6") (pintype "bidirectional+no_connect"))
    )
    (net (code "62") (name "unconnected-(U2-CLKOUT-Pad22)") (class "Default")
      (node (ref "U2") (pin "22") (pinfunction "CLKOUT_22") (pintype "output+no_connect"))
    )
    (net (code "63") (name "unconnected-(U2-NC-Pad2)") (class "Default")
      (node (ref "U2") (pin "2") (pinfunction "NC_2") (pintype "passive+no_connect"))
    )
    (net (code "64") (name "unconnected-(U2-NC-Pad3)") (class "Default")
      (node (ref "U2") (pin "3") (pinfunction "NC_3") (pintype "passive+no_connect"))
    )
    (net (code "65") (name "unconnected-(U2-NC-Pad4)") (class "Default")
      (node (ref "U2") (pin "4") (pinfunction "NC_4") (pintype "passive+no_connect"))
    )
    (net (code "66") (name "unconnected-(U2-NC-Pad5)") (class "Default")
      (node (ref "U2") (pin "5") (pinfunction "NC_5") (pintype "passive+no_connect"))
    )
    (net (code "67") (name "unconnected-(U2-NC-Pad14)") (class "Default")
      (node (ref "U2") (pin "14") (pinfunction "NC_14") (pintype "passive+no_connect"))
    )
    (net (code "68") (name "unconnected-(U2-NC-Pad15)") (class "Default")
      (node (ref "U2") (pin "15") (pinfunction "NC_15") (pintype "passive+no_connect"))
    )
    (net (code "69") (name "unconnected-(U2-NC-Pad16)") (class "Default")
      (node (ref "U2") (pin "16") (pinfunction "NC_16") (pintype "passive+no_connect"))
    )
    (net (code "70") (name "unconnected-(U2-NC-Pad17)") (class "Default")
      (node (ref "U2") (pin "17") (pinfunction "NC_17") (pintype "passive+no_connect"))
    )
    (net (code "71") (name "unconnected-(U2-RESV-Pad19)") (class "Default")
      (node (ref "U2") (pin "19") (pinfunction "RESV_19") (pintype "passive+no_connect"))
    )
    (net (code "72") (name "unconnected-(U2-RESV-Pad21)") (class "Default")
      (node (ref "U2") (pin "21") (pinfunction "RESV_21") (pintype "passive+no_connect"))
    )
  )
)
